# design.net
KiCad netlist of a schematic drawn in Altium Designer
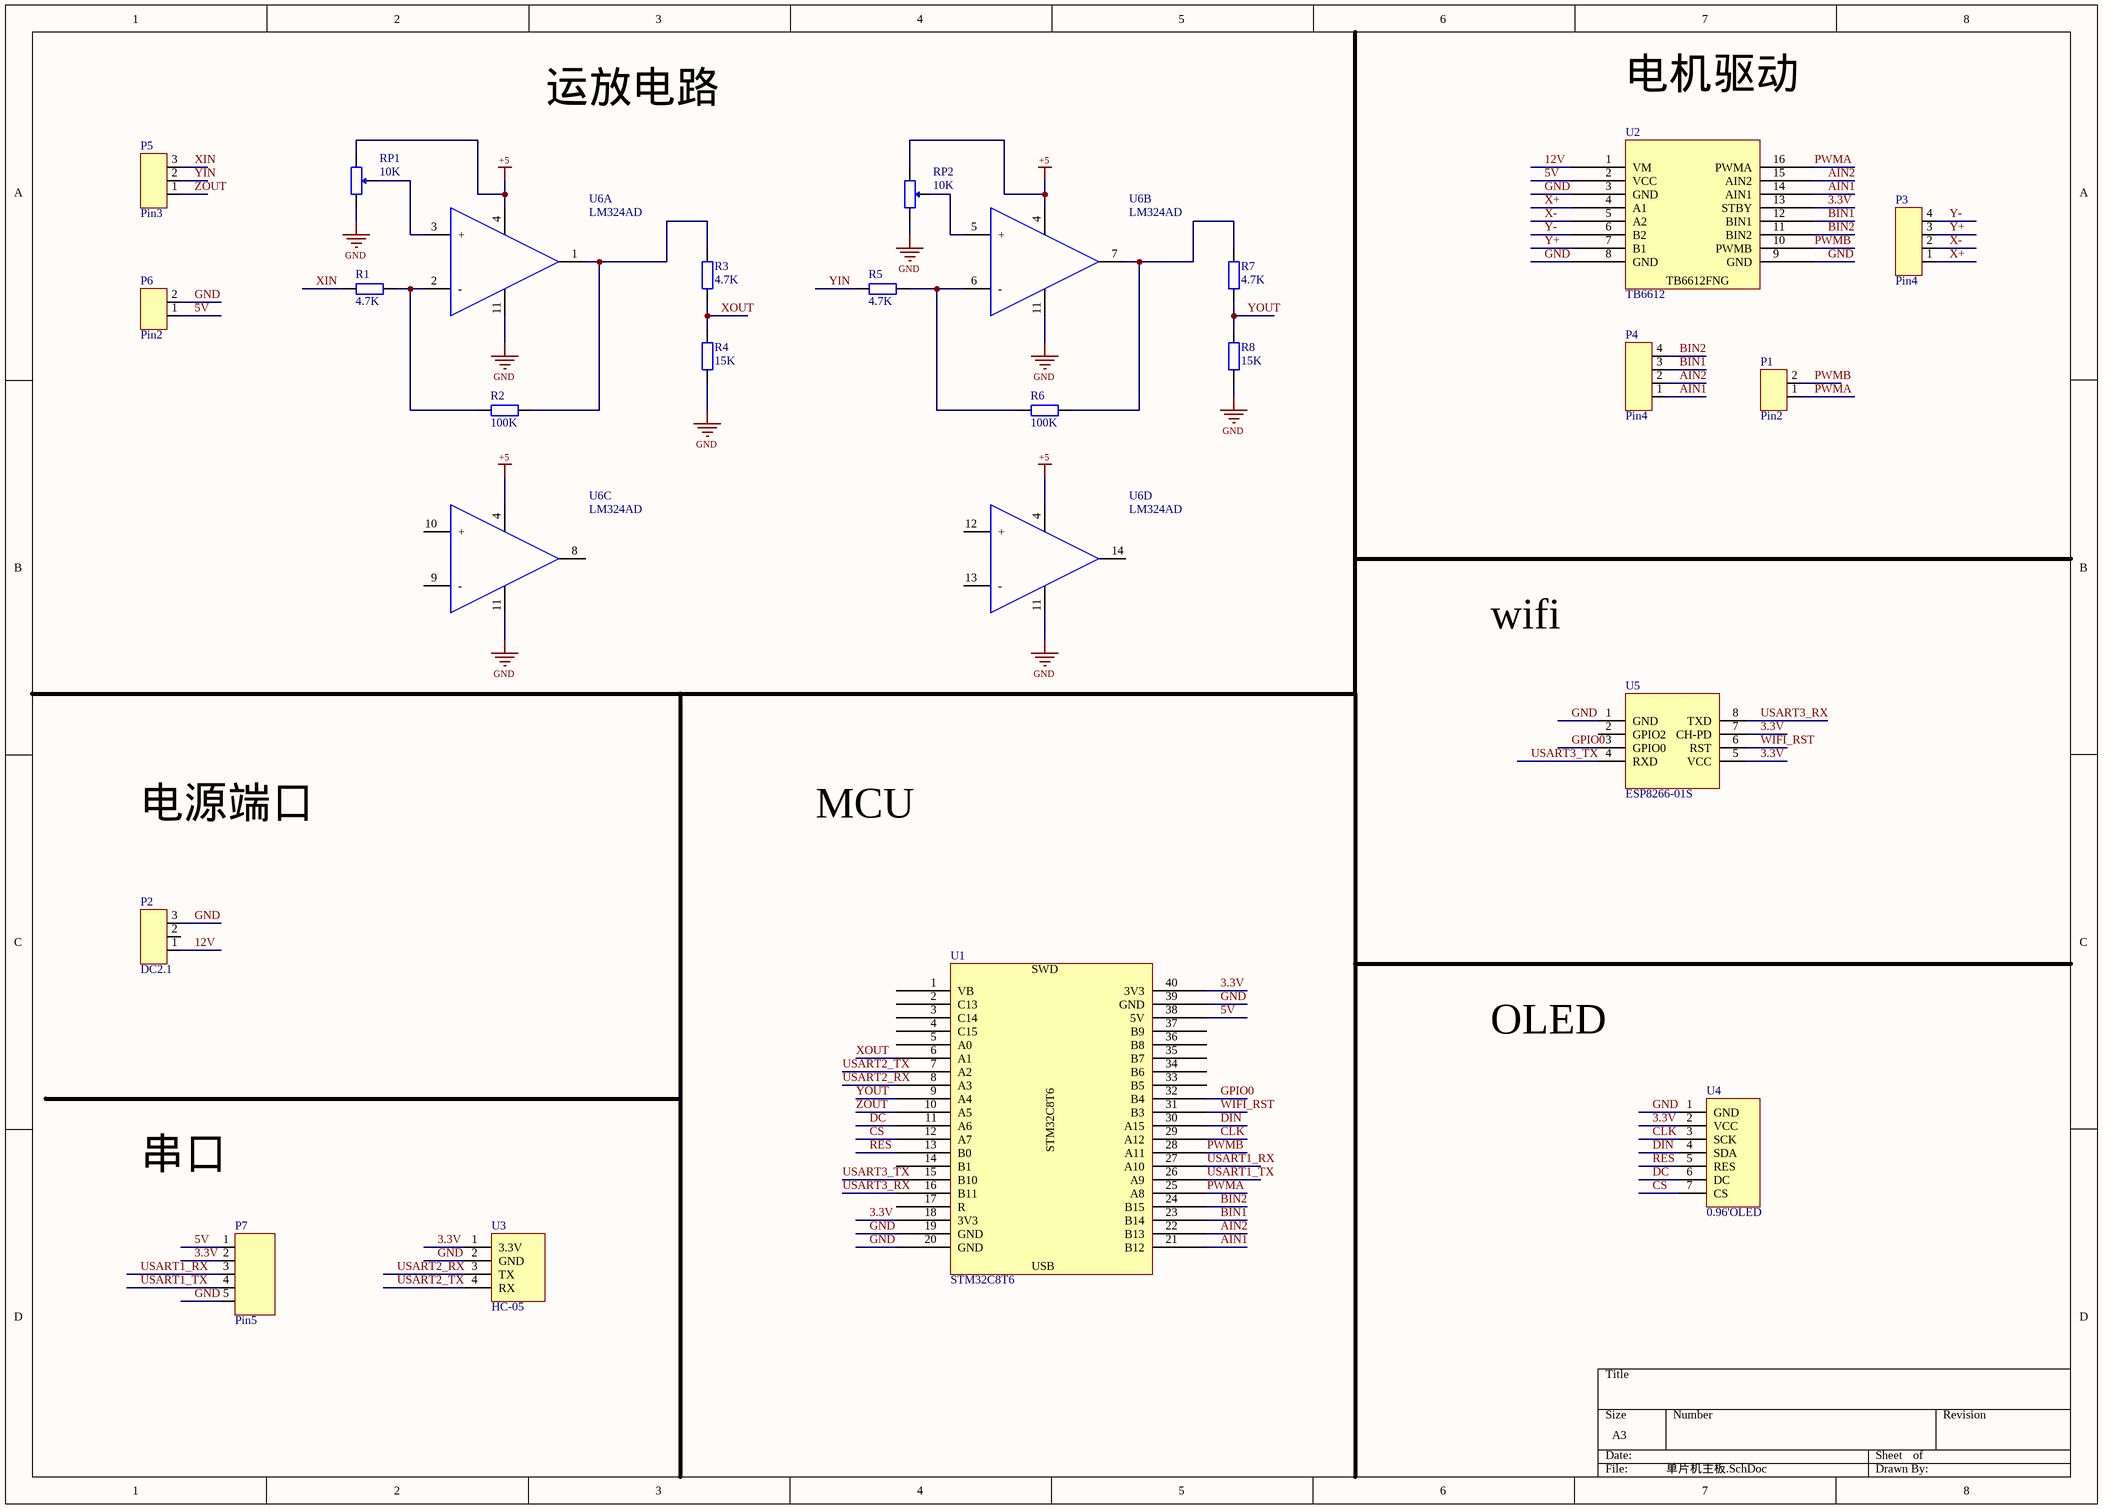
[diagram p0: 单片机主板.SchDoc]

(export (version "E")
  (design (tool "Eeschema 10.0.6"))
  (components
    (comp (ref "P1")
      (value "Pin2")
      (footprint "HDR2.54-LI-2P")
      (description "两脚2.54mm排针")
      (libsource (lib "Schlib1") (part "Pin2"))
    )
    (comp (ref "P2")
      (value "DC2.1")
      (footprint "DC21")
      (description "三脚2.54mm排针")
      (libsource (lib "Schlib1") (part "Pin3"))
    )
    (comp (ref "P3")
      (value "Pin4")
      (footprint "HDR2.54-LI-4P")
      (description "四脚2.54mm排针")
      (libsource (lib "Schlib1") (part "Pin4"))
    )
    (comp (ref "P4")
      (value "Pin4")
      (footprint "HDR2.54-LI-4P")
      (description "四脚2.54mm排针")
      (libsource (lib "Schlib1") (part "Pin4"))
    )
    (comp (ref "P5")
      (value "Pin3")
      (footprint "HDR2.54-LI-3P")
      (description "三脚2.54mm排针")
      (libsource (lib "Schlib1") (part "Pin3"))
    )
    (comp (ref "P6")
      (value "Pin2")
      (footprint "HDR2.54-LI-2P")
      (description "两脚2.54mm排针")
      (libsource (lib "Schlib1") (part "Pin2"))
    )
    (comp (ref "P7")
      (value "Pin5")
      (footprint "HDR2.54-LI-5P")
      (description "五脚2.54mm排针")
      (libsource (lib "Schlib1") (part "Pin5"))
    )
    (comp (ref "R1")
      (value "4.7K")
      (footprint "RS 1/4W")
      (description "直插色环电阻")
      (fields (field (name "版权归属") "源创客"))
      (libsource (lib "3.1   - 电阻-电容-电感") (part "R-CRR"))
    )
    (comp (ref "R2")
      (value "100K")
      (footprint "RS 1/4W")
      (description "直插色环电阻")
      (fields (field (name "版权归属") "源创客"))
      (libsource (lib "3.1   - 电阻-电容-电感") (part "R-CRR"))
    )
    (comp (ref "R3")
      (value "4.7K")
      (footprint "RS 1/4W")
      (description "直插色环电阻")
      (fields (field (name "版权归属") "源创客"))
      (libsource (lib "3.1   - 电阻-电容-电感") (part "R-CRR"))
    )
    (comp (ref "R4")
      (value "15K")
      (footprint "RS 1/4W")
      (description "直插色环电阻")
      (fields (field (name "版权归属") "源创客"))
      (libsource (lib "3.1   - 电阻-电容-电感") (part "R-CRR"))
    )
    (comp (ref "R5")
      (value "4.7K")
      (footprint "RS 1/4W")
      (description "直插色环电阻")
      (fields (field (name "版权归属") "源创客"))
      (libsource (lib "3.1   - 电阻-电容-电感") (part "R-CRR"))
    )
    (comp (ref "R6")
      (value "100K")
      (footprint "RS 1/4W")
      (description "直插色环电阻")
      (fields (field (name "版权归属") "源创客"))
      (libsource (lib "3.1   - 电阻-电容-电感") (part "R-CRR"))
    )
    (comp (ref "R7")
      (value "4.7K")
      (footprint "RS 1/4W")
      (description "直插色环电阻")
      (fields (field (name "版权归属") "源创客"))
      (libsource (lib "3.1   - 电阻-电容-电感") (part "R-CRR"))
    )
    (comp (ref "R8")
      (value "15K")
      (footprint "RS 1/4W")
      (description "直插色环电阻")
      (fields (field (name "版权归属") "源创客"))
      (libsource (lib "3.1   - 电阻-电容-电感") (part "R-CRR"))
    )
    (comp (ref "RP1")
      (value "10K")
      (footprint "3296W")
      (description "插件单联电位器")
      (fields (field (name "版权归属") "源创客"))
      (libsource (lib "3.1   - 电阻-电容-电感") (part "RP-ID"))
    )
    (comp (ref "RP2")
      (value "10K")
      (footprint "3296W")
      (description "插件单联电位器")
      (fields (field (name "版权归属") "源创客"))
      (libsource (lib "3.1   - 电阻-电容-电感") (part "RP-ID"))
    )
    (comp (ref "U1")
      (value "STM32C8T6")
      (footprint "STM32C8T6最小系统板")
      (libsource (lib "STM32C8T6最小系统板") (part "STM32C8T6"))
    )
    (comp (ref "U2") (value "TB6612") (footprint "TB6612") (libsource (lib "模块") (part "TB6612")))
    (comp (ref "U3")
      (value "HC-05")
      (footprint "HC-05")
      (description "蓝牙模块")
      (libsource (lib "模块") (part "HC-05"))
    )
    (comp (ref "U4")
      (value "0.96'OLED")
      (footprint "0.96'OLED")
      (description "OLED显示屏")
      (libsource (lib "模块") (part "0.96'OLED"))
    )
    (comp (ref "U5")
      (value "ESP8266-01S")
      (footprint "ESP8266-01S")
      (description "WIFI模块")
      (libsource (lib "模块") (part "ESP8266-01S"))
    )
    (comp (ref "U6") (value "LM324AD") (footprint "LM324N") (libsource (lib "IC") (part "LM324AD")))
  )
  (nets
    (net (code "1") (name "+5") (class "Default")
      (node (ref "RP1") (pin "1") (pinfunction "1_1") (pintype "passive"))
      (node (ref "RP2") (pin "1") (pinfunction "1_1") (pintype "passive"))
      (node (ref "U6") (pin "4") (pinfunction "VCC_4") (pintype "passive"))
    )
    (net (code "2") (name "/3.3V") (class "Default")
      (node (ref "P7") (pin "2") (pinfunction "2_2") (pintype "passive"))
      (node (ref "U1") (pin "18") (pinfunction "3V3_18") (pintype "passive"))
      (node (ref "U1") (pin "40") (pinfunction "3V3_40") (pintype "passive"))
      (node (ref "U2") (pin "13") (pinfunction "STBY_13") (pintype "passive"))
      (node (ref "U3") (pin "1") (pinfunction "3.3V_1") (pintype "passive"))
      (node (ref "U4") (pin "2") (pinfunction "VCC_2") (pintype "passive"))
      (node (ref "U5") (pin "5") (pinfunction "VCC_5") (pintype "passive"))
      (node (ref "U5") (pin "7") (pinfunction "CH-PD_7") (pintype "passive"))
    )
    (net (code "3") (name "/5V") (class "Default")
      (node (ref "P6") (pin "1") (pinfunction "1_1") (pintype "passive"))
      (node (ref "P7") (pin "1") (pinfunction "1_1") (pintype "passive"))
      (node (ref "U1") (pin "38") (pinfunction "5V_38") (pintype "passive"))
      (node (ref "U2") (pin "2") (pinfunction "VCC_2") (pintype "passive"))
    )
    (net (code "4") (name "/12V") (class "Default")
      (node (ref "P2") (pin "1") (pinfunction "1_1") (pintype "passive"))
      (node (ref "U2") (pin "1") (pinfunction "VM_1") (pintype "passive"))
    )
    (net (code "5") (name "/AIN1") (class "Default")
      (node (ref "P4") (pin "1") (pinfunction "1_1") (pintype "passive"))
      (node (ref "U1") (pin "21") (pinfunction "B12_21") (pintype "passive"))
      (node (ref "U2") (pin "14") (pinfunction "AIN1_14") (pintype "passive"))
    )
    (net (code "6") (name "/AIN2") (class "Default")
      (node (ref "P4") (pin "2") (pinfunction "2_2") (pintype "passive"))
      (node (ref "U1") (pin "22") (pinfunction "B13_22") (pintype "passive"))
      (node (ref "U2") (pin "15") (pinfunction "AIN2_15") (pintype "passive"))
    )
    (net (code "7") (name "/BIN1") (class "Default")
      (node (ref "P4") (pin "3") (pinfunction "3_3") (pintype "passive"))
      (node (ref "U1") (pin "23") (pinfunction "B14_23") (pintype "passive"))
      (node (ref "U2") (pin "12") (pinfunction "BIN1_12") (pintype "passive"))
    )
    (net (code "8") (name "/BIN2") (class "Default")
      (node (ref "P4") (pin "4") (pinfunction "4_4") (pintype "passive"))
      (node (ref "U1") (pin "24") (pinfunction "B15_24") (pintype "passive"))
      (node (ref "U2") (pin "11") (pinfunction "BIN2_11") (pintype "passive"))
    )
    (net (code "9") (name "/CLK") (class "Default")
      (node (ref "U1") (pin "29") (pinfunction "A12_29") (pintype "passive"))
      (node (ref "U4") (pin "3") (pinfunction "SCK_3") (pintype "passive"))
    )
    (net (code "10") (name "/CS") (class "Default")
      (node (ref "U1") (pin "12") (pinfunction "A7_12") (pintype "passive"))
      (node (ref "U4") (pin "7") (pinfunction "CS_7") (pintype "passive"))
    )
    (net (code "11") (name "/DC") (class "Default")
      (node (ref "U1") (pin "11") (pinfunction "A6_11") (pintype "passive"))
      (node (ref "U4") (pin "6") (pinfunction "DC_6") (pintype "passive"))
    )
    (net (code "12") (name "/DIN") (class "Default")
      (node (ref "U1") (pin "30") (pinfunction "A15_30") (pintype "passive"))
      (node (ref "U4") (pin "4") (pinfunction "SDA_4") (pintype "passive"))
    )
    (net (code "13") (name "/GPIO0") (class "Default")
      (node (ref "U1") (pin "32") (pinfunction "B4_32") (pintype "passive"))
      (node (ref "U5") (pin "3") (pinfunction "GPIO0_3") (pintype "passive"))
    )
    (net (code "14") (name "/PWMA") (class "Default")
      (node (ref "P1") (pin "1") (pinfunction "1_1") (pintype "passive"))
      (node (ref "U1") (pin "25") (pinfunction "A8_25") (pintype "passive"))
      (node (ref "U2") (pin "16") (pinfunction "PWMA_16") (pintype "passive"))
    )
    (net (code "15") (name "/PWMB") (class "Default")
      (node (ref "P1") (pin "2") (pinfunction "2_2") (pintype "passive"))
      (node (ref "U1") (pin "28") (pinfunction "A11_28") (pintype "passive"))
      (node (ref "U2") (pin "10") (pinfunction "PWMB_10") (pintype "passive"))
    )
    (net (code "16") (name "/RES") (class "Default")
      (node (ref "U1") (pin "13") (pinfunction "B0_13") (pintype "passive"))
      (node (ref "U4") (pin "5") (pinfunction "RES_5") (pintype "passive"))
    )
    (net (code "17") (name "/USART1_RX") (class "Default")
      (node (ref "P7") (pin "3") (pinfunction "3_3") (pintype "passive"))
      (node (ref "U1") (pin "27") (pinfunction "A10_27") (pintype "passive"))
    )
    (net (code "18") (name "/USART1_TX") (class "Default")
      (node (ref "P7") (pin "4") (pinfunction "4_4") (pintype "passive"))
      (node (ref "U1") (pin "26") (pinfunction "A9_26") (pintype "passive"))
    )
    (net (code "19") (name "/USART2_RX") (class "Default")
      (node (ref "U1") (pin "8") (pinfunction "A3_8") (pintype "passive"))
      (node (ref "U3") (pin "3") (pinfunction "TX_3") (pintype "passive"))
    )
    (net (code "20") (name "/USART2_TX") (class "Default")
      (node (ref "U1") (pin "7") (pinfunction "A2_7") (pintype "passive"))
      (node (ref "U3") (pin "4") (pinfunction "RX_4") (pintype "passive"))
    )
    (net (code "21") (name "/USART3_RX") (class "Default")
      (node (ref "U1") (pin "16") (pinfunction "B11_16") (pintype "passive"))
      (node (ref "U5") (pin "8") (pinfunction "TXD_8") (pintype "passive"))
    )
    (net (code "22") (name "/USART3_TX") (class "Default")
      (node (ref "U1") (pin "15") (pinfunction "B10_15") (pintype "passive"))
      (node (ref "U5") (pin "4") (pinfunction "RXD_4") (pintype "passive"))
    )
    (net (code "23") (name "/WIFI_RST") (class "Default")
      (node (ref "U1") (pin "31") (pinfunction "B3_31") (pintype "passive"))
      (node (ref "U5") (pin "6") (pinfunction "RST_6") (pintype "passive"))
    )
    (net (code "24") (name "/X+") (class "Default")
      (node (ref "P3") (pin "1") (pinfunction "1_1") (pintype "passive"))
      (node (ref "U2") (pin "4") (pinfunction "A1_4") (pintype "passive"))
    )
    (net (code "25") (name "/X-") (class "Default")
      (node (ref "P3") (pin "2") (pinfunction "2_2") (pintype "passive"))
      (node (ref "U2") (pin "5") (pinfunction "A2_5") (pintype "passive"))
    )
    (net (code "26") (name "/XIN") (class "Default")
      (node (ref "P5") (pin "3") (pinfunction "3_3") (pintype "passive"))
      (node (ref "R1") (pin "1") (pinfunction "1_1") (pintype "passive"))
    )
    (net (code "27") (name "/XOUT") (class "Default")
      (node (ref "R3") (pin "1") (pinfunction "1_1") (pintype "passive"))
      (node (ref "R4") (pin "2") (pinfunction "2_2") (pintype "passive"))
      (node (ref "U1") (pin "6") (pinfunction "A1_6") (pintype "passive"))
    )
    (net (code "28") (name "/Y+") (class "Default")
      (node (ref "P3") (pin "3") (pinfunction "3_3") (pintype "passive"))
      (node (ref "U2") (pin "7") (pinfunction "B1_7") (pintype "passive"))
    )
    (net (code "29") (name "/Y-") (class "Default")
      (node (ref "P3") (pin "4") (pinfunction "4_4") (pintype "passive"))
      (node (ref "U2") (pin "6") (pinfunction "B2_6") (pintype "passive"))
    )
    (net (code "30") (name "/YIN") (class "Default")
      (node (ref "P5") (pin "2") (pinfunction "2_2") (pintype "passive"))
      (node (ref "R5") (pin "1") (pinfunction "1_1") (pintype "passive"))
    )
    (net (code "31") (name "/YOUT") (class "Default")
      (node (ref "R7") (pin "1") (pinfunction "1_1") (pintype "passive"))
      (node (ref "R8") (pin "2") (pinfunction "2_2") (pintype "passive"))
      (node (ref "U1") (pin "9") (pinfunction "A4_9") (pintype "passive"))
    )
    (net (code "32") (name "/ZOUT") (class "Default")
      (node (ref "P5") (pin "1") (pinfunction "1_1") (pintype "passive"))
      (node (ref "U1") (pin "10") (pinfunction "A5_10") (pintype "passive"))
    )
    (net (code "33") (name "GND") (class "Default")
      (node (ref "P2") (pin "3") (pinfunction "3_3") (pintype "passive"))
      (node (ref "P6") (pin "2") (pinfunction "2_2") (pintype "passive"))
      (node (ref "P7") (pin "5") (pinfunction "5_5") (pintype "passive"))
      (node (ref "R4") (pin "1") (pinfunction "1_1") (pintype "passive"))
      (node (ref "R8") (pin "1") (pinfunction "1_1") (pintype "passive"))
      (node (ref "RP1") (pin "3") (pinfunction "3_3") (pintype "passive"))
      (node (ref "RP2") (pin "3") (pinfunction "3_3") (pintype "passive"))
      (node (ref "U1") (pin "19") (pinfunction "GND_19") (pintype "passive"))
      (node (ref "U1") (pin "20") (pinfunction "GND_20") (pintype "passive"))
      (node (ref "U1") (pin "39") (pinfunction "GND_39") (pintype "passive"))
      (node (ref "U2") (pin "3") (pinfunction "GND_3") (pintype "passive"))
      (node (ref "U2") (pin "8") (pinfunction "GND_8") (pintype "passive"))
      (node (ref "U2") (pin "9") (pinfunction "GND_9") (pintype "passive"))
      (node (ref "U3") (pin "2") (pinfunction "GND_2") (pintype "passive"))
      (node (ref "U4") (pin "1") (pinfunction "GND_1") (pintype "passive"))
      (node (ref "U5") (pin "1") (pinfunction "GND_1") (pintype "passive"))
      (node (ref "U6") (pin "11") (pinfunction "GND_11") (pintype "passive"))
    )
    (net (code "34") (name "Net-(R2-Pad2)") (class "Default")
      (node (ref "R2") (pin "2") (pinfunction "2_2") (pintype "passive"))
      (node (ref "R3") (pin "2") (pinfunction "2_2") (pintype "passive"))
      (node (ref "U6") (pin "1") (pinfunction "1_1") (pintype "passive"))
    )
    (net (code "35") (name "Net-(R6-Pad2)") (class "Default")
      (node (ref "R6") (pin "2") (pinfunction "2_2") (pintype "passive"))
      (node (ref "R7") (pin "2") (pinfunction "2_2") (pintype "passive"))
      (node (ref "U6") (pin "7") (pinfunction "7_7") (pintype "passive"))
    )
    (net (code "36") (name "Net-(U6A-+)") (class "Default")
      (node (ref "RP1") (pin "2") (pinfunction "2_2") (pintype "passive"))
      (node (ref "U6") (pin "3") (pinfunction "+_3") (pintype "passive"))
    )
    (net (code "37") (name "Net-(U6A--)") (class "Default")
      (node (ref "R1") (pin "2") (pinfunction "2_2") (pintype "passive"))
      (node (ref "R2") (pin "1") (pinfunction "1_1") (pintype "passive"))
      (node (ref "U6") (pin "2") (pinfunction "-_2") (pintype "passive"))
    )
    (net (code "38") (name "Net-(U6B-+)") (class "Default")
      (node (ref "RP2") (pin "2") (pinfunction "2_2") (pintype "passive"))
      (node (ref "U6") (pin "5") (pinfunction "+_5") (pintype "passive"))
    )
    (net (code "39") (name "Net-(U6B--)") (class "Default")
      (node (ref "R5") (pin "2") (pinfunction "2_2") (pintype "passive"))
      (node (ref "R6") (pin "1") (pinfunction "1_1") (pintype "passive"))
      (node (ref "U6") (pin "6") (pinfunction "-_6") (pintype "passive"))
    )
    (net (code "40") (name "unconnected-(P2-Pad2)") (class "Default")
      (node (ref "P2") (pin "2") (pinfunction "2_2") (pintype "passive"))
    )
    (net (code "41") (name "unconnected-(U1-A0-Pad5)") (class "Default")
      (node (ref "U1") (pin "5") (pinfunction "A0_5") (pintype "passive"))
    )
    (net (code "42") (name "unconnected-(U1-B1-Pad14)") (class "Default")
      (node (ref "U1") (pin "14") (pinfunction "B1_14") (pintype "passive"))
    )
    (net (code "43") (name "unconnected-(U1-B5-Pad33)") (class "Default")
      (node (ref "U1") (pin "33") (pinfunction "B5_33") (pintype "passive"))
    )
    (net (code "44") (name "unconnected-(U1-B6-Pad34)") (class "Default")
      (node (ref "U1") (pin "34") (pinfunction "B6_34") (pintype "passive"))
    )
    (net (code "45") (name "unconnected-(U1-B7-Pad35)") (class "Default")
      (node (ref "U1") (pin "35") (pinfunction "B7_35") (pintype "passive"))
    )
    (net (code "46") (name "unconnected-(U1-B8-Pad36)") (class "Default")
      (node (ref "U1") (pin "36") (pinfunction "B8_36") (pintype "passive"))
    )
    (net (code "47") (name "unconnected-(U1-B9-Pad37)") (class "Default")
      (node (ref "U1") (pin "37") (pinfunction "B9_37") (pintype "passive"))
    )
    (net (code "48") (name "unconnected-(U1-C13-Pad2)") (class "Default")
      (node (ref "U1") (pin "2") (pinfunction "C13_2") (pintype "passive"))
    )
    (net (code "49") (name "unconnected-(U1-C14-Pad3)") (class "Default")
      (node (ref "U1") (pin "3") (pinfunction "C14_3") (pintype "passive"))
    )
    (net (code "50") (name "unconnected-(U1-C15-Pad4)") (class "Default")
      (node (ref "U1") (pin "4") (pinfunction "C15_4") (pintype "passive"))
    )
    (net (code "51") (name "unconnected-(U1-R-Pad17)") (class "Default")
      (node (ref "U1") (pin "17") (pinfunction "R_17") (pintype "passive"))
    )
    (net (code "52") (name "unconnected-(U1-VB-Pad1)") (class "Default")
      (node (ref "U1") (pin "1") (pinfunction "VB_1") (pintype "passive"))
    )
    (net (code "53") (name "unconnected-(U5-GPIO2-Pad2)") (class "Default")
      (node (ref "U5") (pin "2") (pinfunction "GPIO2_2") (pintype "passive"))
    )
    (net (code "54") (name "unconnected-(U6-Pad8)") (class "Default")
      (node (ref "U6") (pin "8") (pinfunction "8_8") (pintype "passive"))
    )
    (net (code "55") (name "unconnected-(U6-Pad14)") (class "Default")
      (node (ref "U6") (pin "14") (pinfunction "14_14") (pintype "passive"))
    )
    (net (code "56") (name "unconnected-(U6C-+-Pad10)") (class "Default")
      (node (ref "U6") (pin "10") (pinfunction "+_10") (pintype "passive"))
    )
    (net (code "57") (name "unconnected-(U6C---Pad9)") (class "Default")
      (node (ref "U6") (pin "9") (pinfunction "-_9") (pintype "passive"))
    )
    (net (code "58") (name "unconnected-(U6D-+-Pad12)") (class "Default")
      (node (ref "U6") (pin "12") (pinfunction "+_12") (pintype "passive"))
    )
    (net (code "59") (name "unconnected-(U6D---Pad13)") (class "Default")
      (node (ref "U6") (pin "13") (pinfunction "-_13") (pintype "passive"))
    )
  )
)
